# mag_encoder_Rev2.net
KiCad netlist of a schematic drawn in EAGLE
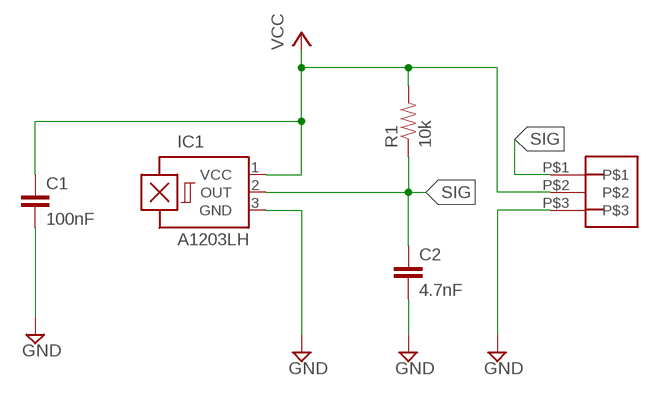
[diagram p0: schematic, sheet 1]

(export (version "E")
  (design (tool "Eeschema 10.0.6"))
  (components
    (comp (ref "C1")
      (value "100nF")
      (footprint "eagle-import:0603-CAP")
      (libsource (lib "eagle-import") (part "CAP0603-CAP"))
    )
    (comp (ref "C2")
      (value "4.7nF")
      (footprint "eagle-import:0603-CAP")
      (libsource (lib "eagle-import") (part "4.7NF-50V-10%(0603)"))
    )
    (comp (ref "IC1")
      (value "A1203LH")
      (footprint "eagle-import:SOT23-W")
      (fields (field (name "MF") "ALLEGRO MICROSYSTEMS, INC.") (field (name "MPN") "A1203LLHLT-T"))
      (libsource (lib "eagle-import") (part "A12?LH03"))
    )
    (comp (ref "R1")
      (value "10k")
      (footprint "eagle-import:0603")
      (libsource (lib "eagle-import") (part "10.5KOHM1/10W1%(0603)"))
    )
    (comp (ref "U$1")
      (value "3_PIN_JST-XH")
      (footprint "eagle-import:3_PIN_JST-XH")
      (libsource (lib "eagle-import") (part "3_PIN_JST-XH"))
    )
  )
  (nets
    (net (code "1") (name "GND") (class "Default")
      (node (ref "C1") (pin "2") (pinfunction "2_2") (pintype "passive"))
      (node (ref "C2") (pin "2") (pinfunction "2_2") (pintype "passive"))
      (node (ref "IC1") (pin "3") (pinfunction "GND_3") (pintype "power_in"))
      (node (ref "U$1") (pin "P$3") (pinfunction "P$3_P$3") (pintype "bidirectional"))
    )
    (net (code "2") (name "SIG") (class "Default")
      (node (ref "C2") (pin "1") (pinfunction "1_1") (pintype "passive"))
      (node (ref "IC1") (pin "2") (pinfunction "OUT_2") (pintype "output"))
      (node (ref "R1") (pin "1") (pinfunction "1_1") (pintype "passive"))
      (node (ref "U$1") (pin "P$1") (pinfunction "P$1_P$1") (pintype "bidirectional"))
    )
    (net (code "3") (name "VCC") (class "Default")
      (node (ref "C1") (pin "1") (pinfunction "1_1") (pintype "passive"))
      (node (ref "IC1") (pin "1") (pinfunction "VCC_1") (pintype "power_in"))
      (node (ref "R1") (pin "2") (pinfunction "2_2") (pintype "passive"))
      (node (ref "U$1") (pin "P$2") (pinfunction "P$2_P$2") (pintype "bidirectional"))
    )
  )
)
